# IO_V1_0.net
KiCad netlist of a schematic drawn in EAGLE
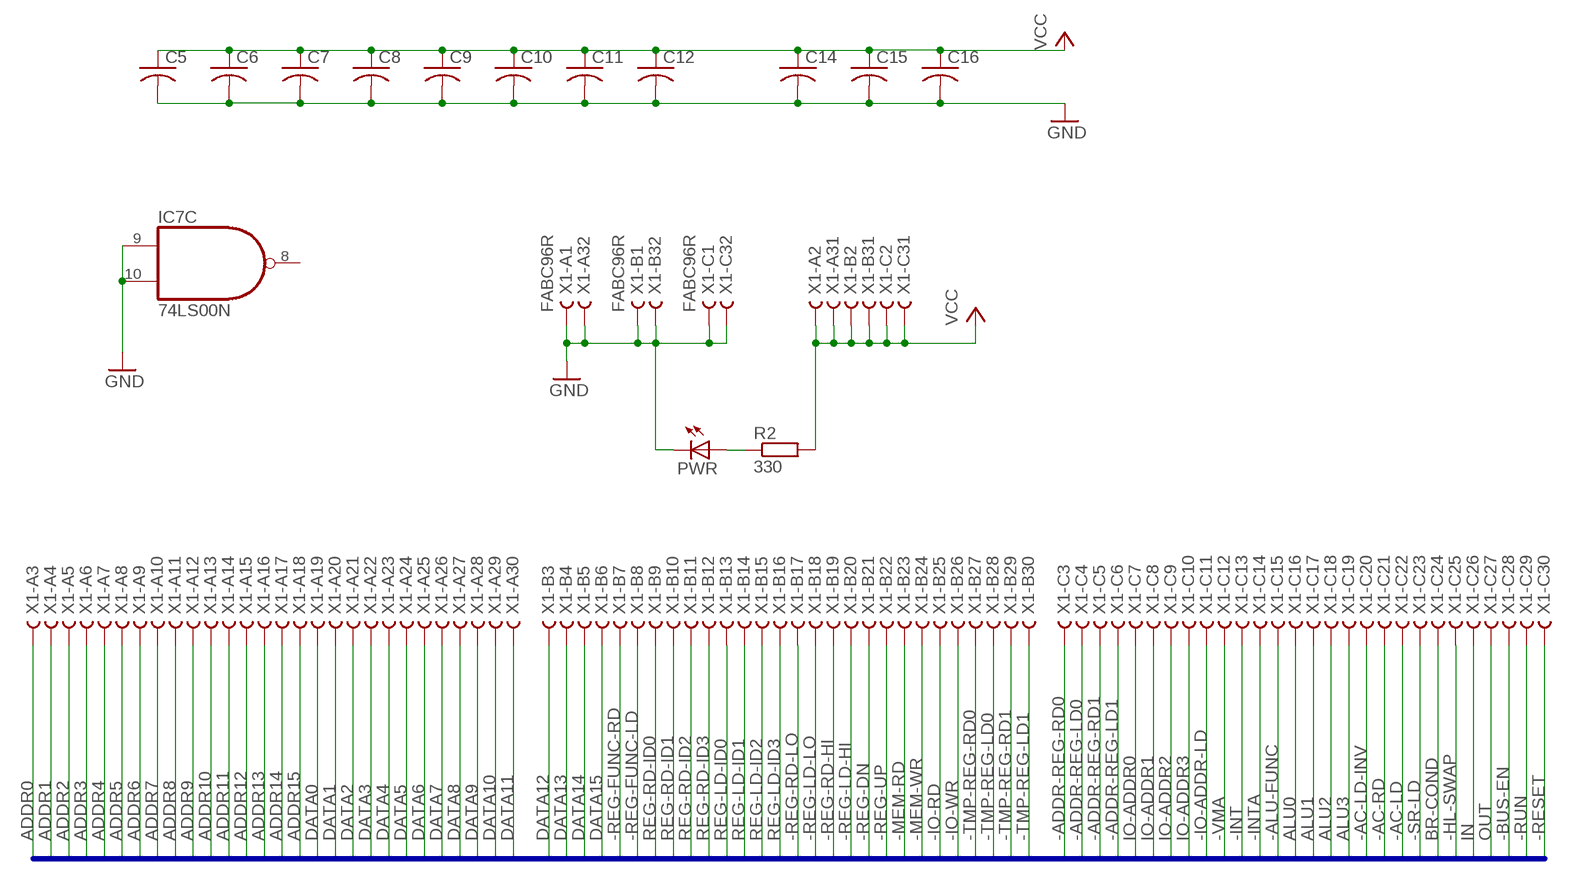
[diagram p0: schematic, sheet 1]
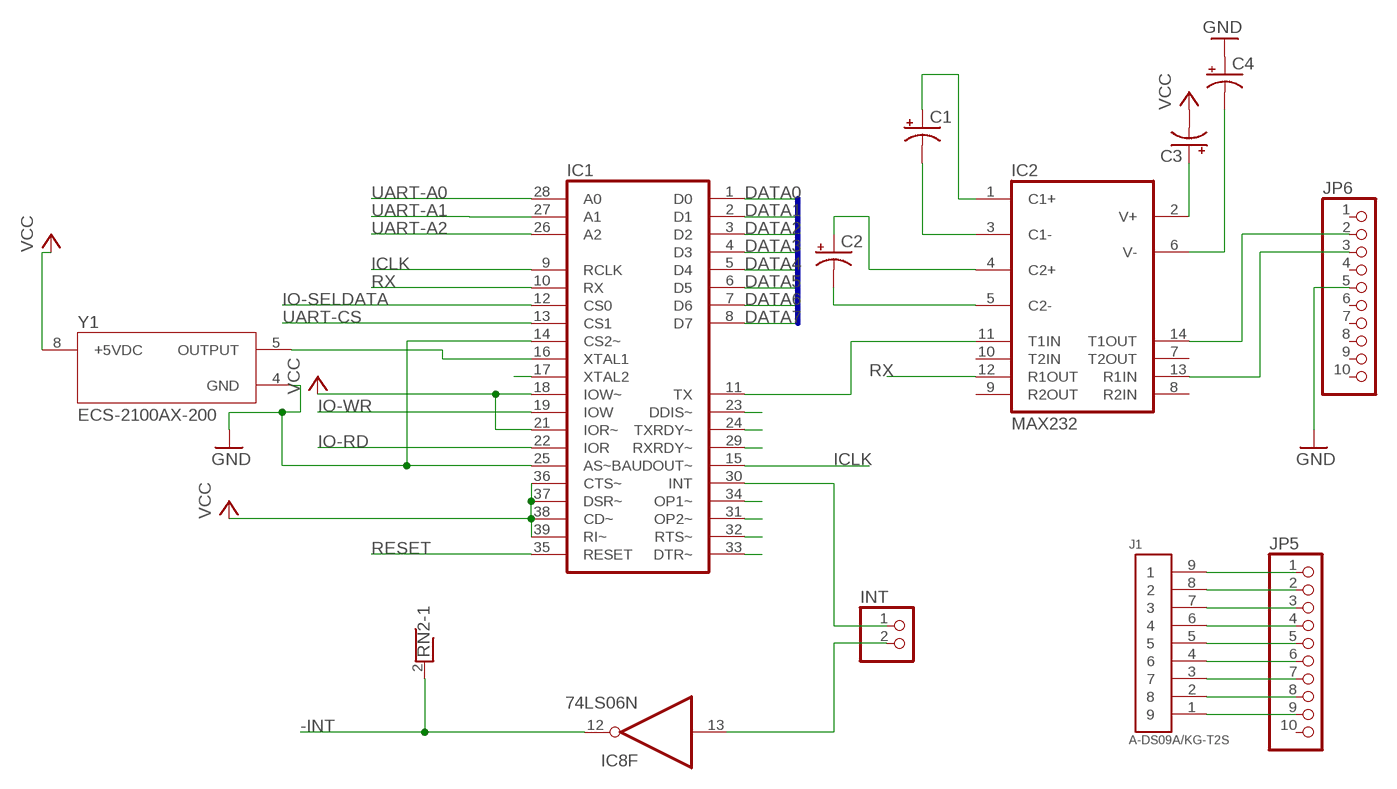
[diagram p1: schematic, sheet 2]
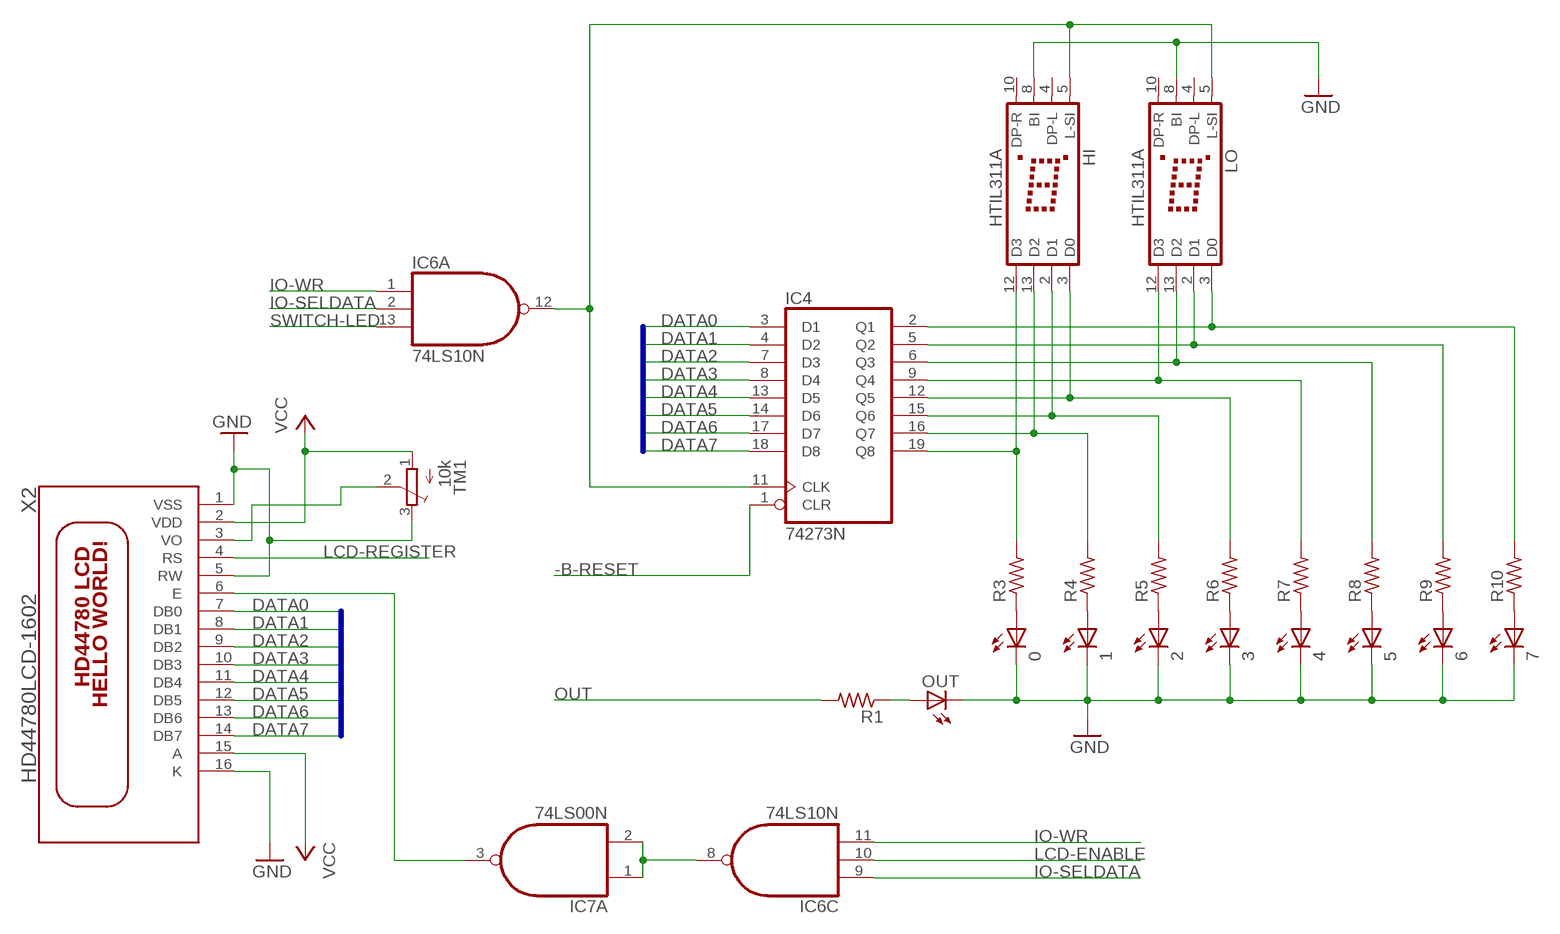
[diagram p2: schematic, sheet 3]
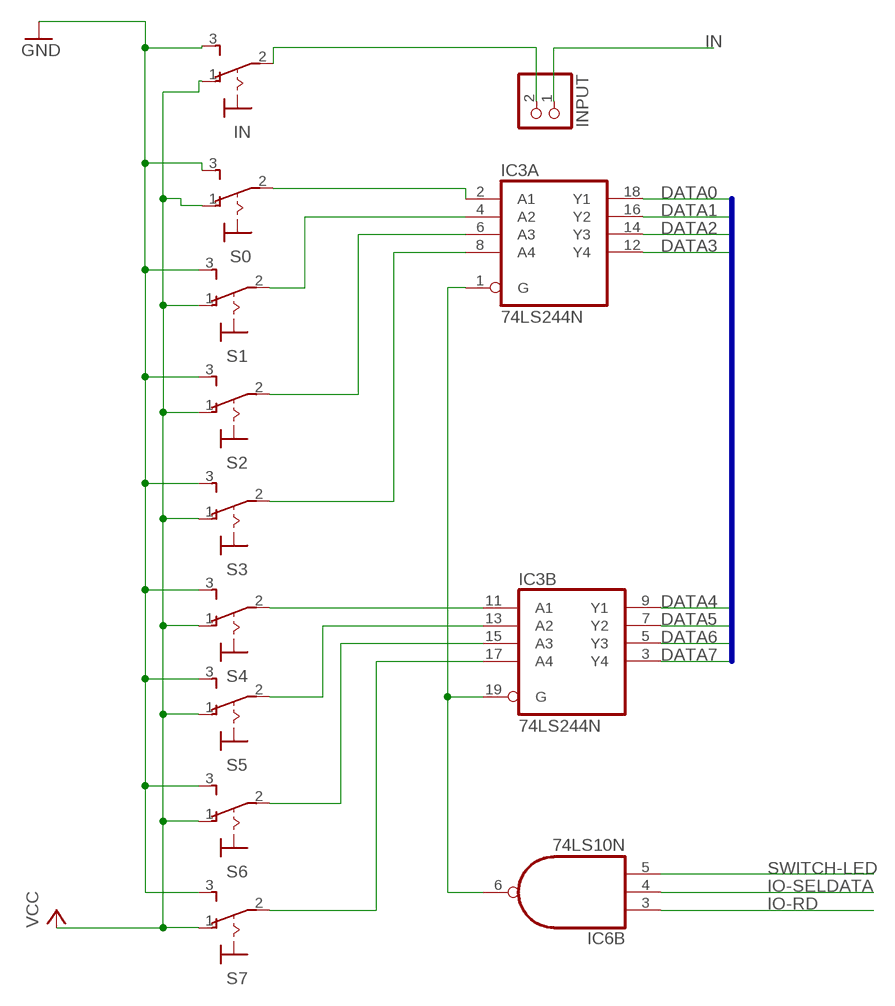
[diagram p3: schematic, sheet 4]
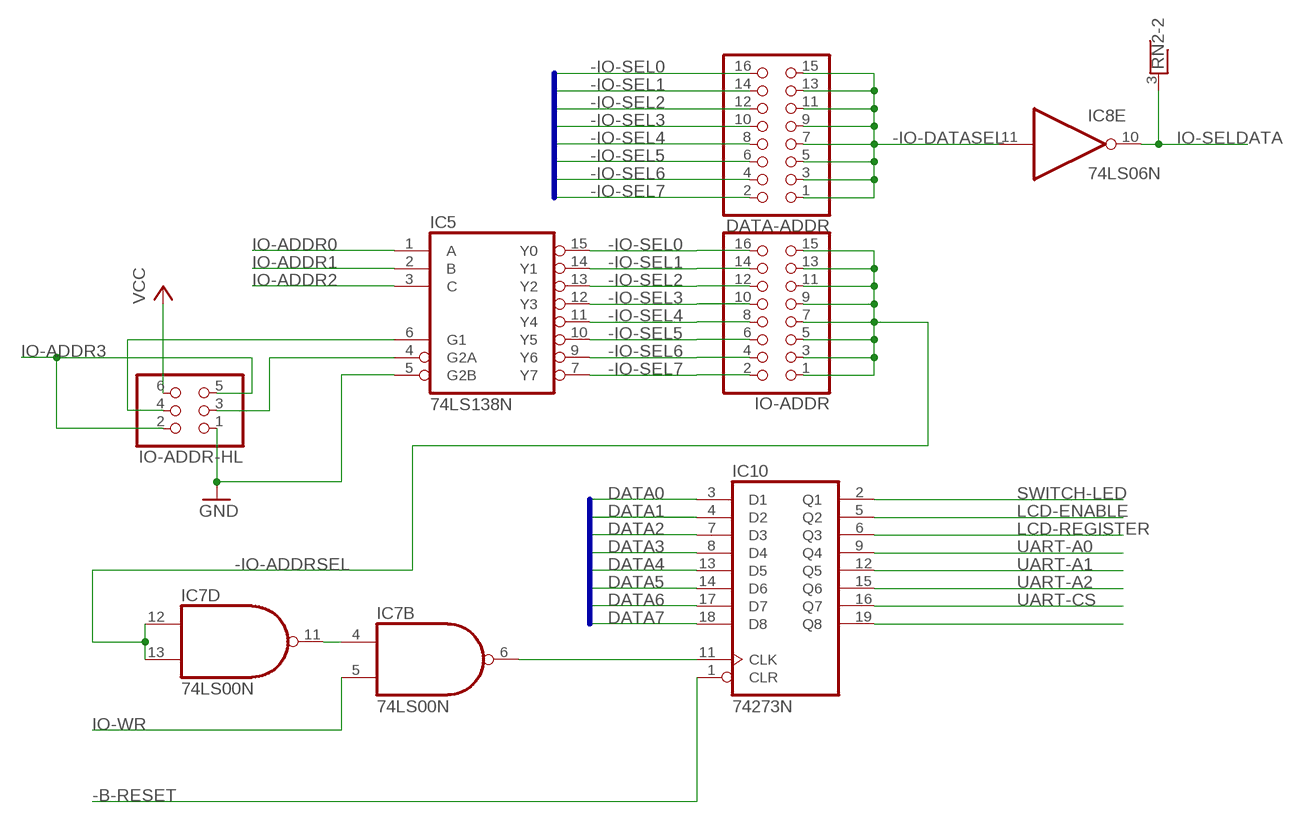
[diagram p4: schematic, sheet 5]
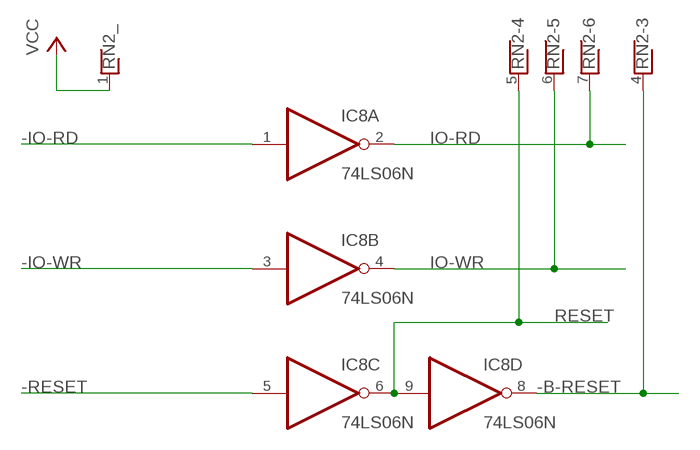
[diagram p5: schematic, sheet 6]

(export (version "E")
  (design (tool "Eeschema 10.0.6"))
  (components
    (comp (ref "C5")
      (value "C-US025-024X044")
      (footprint "eagle-import:C025-024X044")
      (libsource (lib "eagle-import") (part "C-US025-024X044"))
    )
    (comp (ref "C6")
      (value "C-US025-024X044")
      (footprint "eagle-import:C025-024X044")
      (libsource (lib "eagle-import") (part "C-US025-024X044"))
    )
    (comp (ref "C7")
      (value "C-US025-024X044")
      (footprint "eagle-import:C025-024X044")
      (libsource (lib "eagle-import") (part "C-US025-024X044"))
    )
    (comp (ref "C8")
      (value "C-US025-024X044")
      (footprint "eagle-import:C025-024X044")
      (libsource (lib "eagle-import") (part "C-US025-024X044"))
    )
    (comp (ref "C9")
      (value "C-US025-024X044")
      (footprint "eagle-import:C025-024X044")
      (libsource (lib "eagle-import") (part "C-US025-024X044"))
    )
    (comp (ref "C10")
      (value "C-US025-024X044")
      (footprint "eagle-import:C025-024X044")
      (libsource (lib "eagle-import") (part "C-US025-024X044"))
    )
    (comp (ref "C11")
      (value "C-US025-024X044")
      (footprint "eagle-import:C025-024X044")
      (libsource (lib "eagle-import") (part "C-US025-024X044"))
    )
    (comp (ref "C12")
      (value "C-US025-024X044")
      (footprint "eagle-import:C025-024X044")
      (libsource (lib "eagle-import") (part "C-US025-024X044"))
    )
    (comp (ref "C14")
      (value "C-US025-024X044")
      (footprint "eagle-import:C025-024X044")
      (libsource (lib "eagle-import") (part "C-US025-024X044"))
    )
    (comp (ref "C15")
      (value "C-US025-024X044")
      (footprint "eagle-import:C025-024X044")
      (libsource (lib "eagle-import") (part "C-US025-024X044"))
    )
    (comp (ref "C16")
      (value "C-US025-024X044")
      (footprint "eagle-import:C025-024X044")
      (libsource (lib "eagle-import") (part "C-US025-024X044"))
    )
    (comp (ref "IC7")
      (value "74LS00N")
      (footprint "eagle-import:DIL14")
      (libsource (lib "eagle-import") (part "7400NLS"))
    )
    (comp (ref "PWR")
      (value "LED5MM")
      (footprint "eagle-import:LED5MM")
      (libsource (lib "eagle-import") (part "led_LED5MM"))
    )
    (comp (ref "R2")
      (value "330")
      (footprint "eagle-import:0207_10")
      (libsource (lib "eagle-import") (part "R0207/10"))
    )
    (comp (ref "X1")
      (value "FABC96R")
      (footprint "eagle-import:FABC96R")
      (libsource (lib "eagle-import") (part "FABC96R"))
    )
    (comp (ref "DATA-ADDR")
      (value "PINHD-2X8")
      (footprint "eagle-import:2X08")
      (libsource (lib "eagle-import") (part "PINHD-2X8"))
    )
    (comp (ref "IC5")
      (value "74LS138N")
      (footprint "eagle-import:DIL16")
      (libsource (lib "eagle-import") (part "74138NLS"))
    )
    (comp (ref "IC8")
      (value "74LS06N")
      (footprint "eagle-import:DIL14")
      (libsource (lib "eagle-import") (part "7406NLS"))
    )
    (comp (ref "IC10")
      (value "74273N")
      (footprint "eagle-import:DIL20")
      (libsource (lib "eagle-import") (part "74273N"))
    )
    (comp (ref "IO-ADDR")
      (value "PINHD-2X8")
      (footprint "eagle-import:2X08")
      (libsource (lib "eagle-import") (part "PINHD-2X8"))
    )
    (comp (ref "IO-ADDR-HL")
      (value "PINHD-2X3")
      (footprint "eagle-import:2X03")
      (libsource (lib "eagle-import") (part "PINHD-2X3"))
    )
    (comp (ref "RN2")
      (value "RNX6")
      (footprint "eagle-import:RN-7")
      (libsource (lib "eagle-import") (part "RNX6"))
    )
    (comp (ref "0")
      (value "LED5MM")
      (footprint "eagle-import:LED5MM")
      (libsource (lib "eagle-import") (part "LED5MM"))
    )
    (comp (ref "1")
      (value "LED5MM")
      (footprint "eagle-import:LED5MM")
      (libsource (lib "eagle-import") (part "LED5MM"))
    )
    (comp (ref "2")
      (value "LED5MM")
      (footprint "eagle-import:LED5MM")
      (libsource (lib "eagle-import") (part "LED5MM"))
    )
    (comp (ref "3")
      (value "LED5MM")
      (footprint "eagle-import:LED5MM")
      (libsource (lib "eagle-import") (part "LED5MM"))
    )
    (comp (ref "4")
      (value "LED5MM")
      (footprint "eagle-import:LED5MM")
      (libsource (lib "eagle-import") (part "LED5MM"))
    )
    (comp (ref "5")
      (value "LED5MM")
      (footprint "eagle-import:LED5MM")
      (libsource (lib "eagle-import") (part "LED5MM"))
    )
    (comp (ref "6")
      (value "LED5MM")
      (footprint "eagle-import:LED5MM")
      (libsource (lib "eagle-import") (part "LED5MM"))
    )
    (comp (ref "7")
      (value "LED5MM")
      (footprint "eagle-import:LED5MM")
      (libsource (lib "eagle-import") (part "LED5MM"))
    )
    (comp (ref "HI")
      (value "HTIL311A")
      (footprint "eagle-import:HTIL311A")
      (libsource (lib "eagle-import") (part "HTIL311A"))
    )
    (comp (ref "IC4")
      (value "74273N")
      (footprint "eagle-import:DIL20")
      (libsource (lib "eagle-import") (part "74273N"))
    )
    (comp (ref "IC6")
      (value "74LS10N")
      (footprint "eagle-import:DIL14")
      (libsource (lib "eagle-import") (part "7410NLS"))
    )
    (comp (ref "LO")
      (value "HTIL311A")
      (footprint "eagle-import:HTIL311A")
      (libsource (lib "eagle-import") (part "HTIL311A"))
    )
    (comp (ref "OUT")
      (value "LED5MM")
      (footprint "eagle-import:LED5MM")
      (libsource (lib "eagle-import") (part "LED5MM"))
    )
    (comp (ref "R1")
      (value "R-US_0207/10")
      (footprint "eagle-import:0207_10")
      (libsource (lib "eagle-import") (part "R-US_0207/10"))
    )
    (comp (ref "R3")
      (value "R-US_0207/10")
      (footprint "eagle-import:0207_10")
      (libsource (lib "eagle-import") (part "R-US_0207/10"))
    )
    (comp (ref "R4")
      (value "R-US_0207/10")
      (footprint "eagle-import:0207_10")
      (libsource (lib "eagle-import") (part "R-US_0207/10"))
    )
    (comp (ref "R5")
      (value "R-US_0207/10")
      (footprint "eagle-import:0207_10")
      (libsource (lib "eagle-import") (part "R-US_0207/10"))
    )
    (comp (ref "R6")
      (value "R-US_0207/10")
      (footprint "eagle-import:0207_10")
      (libsource (lib "eagle-import") (part "R-US_0207/10"))
    )
    (comp (ref "R7")
      (value "R-US_0207/10")
      (footprint "eagle-import:0207_10")
      (libsource (lib "eagle-import") (part "R-US_0207/10"))
    )
    (comp (ref "R8")
      (value "R-US_0207/10")
      (footprint "eagle-import:0207_10")
      (libsource (lib "eagle-import") (part "R-US_0207/10"))
    )
    (comp (ref "R9")
      (value "R-US_0207/10")
      (footprint "eagle-import:0207_10")
      (libsource (lib "eagle-import") (part "R-US_0207/10"))
    )
    (comp (ref "R10")
      (value "R-US_0207/10")
      (footprint "eagle-import:0207_10")
      (libsource (lib "eagle-import") (part "R-US_0207/10"))
    )
    (comp (ref "TM1")
      (value "10k")
      (footprint "eagle-import:TRIM-3386")
      (libsource (lib "eagle-import") (part "TRIMPOT3386"))
    )
    (comp (ref "X2")
      (value "HD44780LCD-1602")
      (footprint "eagle-import:LCD1602")
      (libsource (lib "eagle-import") (part "HD44780LCD-1602"))
    )
    (comp (ref "IC3")
      (value "74LS244N")
      (footprint "eagle-import:DIL20")
      (libsource (lib "eagle-import") (part "74xx-us_88_74244NLS"))
    )
    (comp (ref "IN")
      (value "M9040P")
      (footprint "eagle-import:M9040P")
      (libsource (lib "eagle-import") (part "M9040P"))
    )
    (comp (ref "INPUT")
      (value "PINHD-1X2")
      (footprint "eagle-import:1X02")
      (libsource (lib "eagle-import") (part "PINHD-1X2"))
    )
    (comp (ref "S0")
      (value "M9040P")
      (footprint "eagle-import:M9040P")
      (libsource (lib "eagle-import") (part "M9040P"))
    )
    (comp (ref "S1")
      (value "M9040P")
      (footprint "eagle-import:M9040P")
      (libsource (lib "eagle-import") (part "M9040P"))
    )
    (comp (ref "S2")
      (value "M9040P")
      (footprint "eagle-import:M9040P")
      (libsource (lib "eagle-import") (part "M9040P"))
    )
    (comp (ref "S3")
      (value "M9040P")
      (footprint "eagle-import:M9040P")
      (libsource (lib "eagle-import") (part "M9040P"))
    )
    (comp (ref "S4")
      (value "M9040P")
      (footprint "eagle-import:M9040P")
      (libsource (lib "eagle-import") (part "M9040P"))
    )
    (comp (ref "S5")
      (value "M9040P")
      (footprint "eagle-import:M9040P")
      (libsource (lib "eagle-import") (part "M9040P"))
    )
    (comp (ref "S6")
      (value "M9040P")
      (footprint "eagle-import:M9040P")
      (libsource (lib "eagle-import") (part "M9040P"))
    )
    (comp (ref "S7")
      (value "M9040P")
      (footprint "eagle-import:M9040P")
      (libsource (lib "eagle-import") (part "M9040P"))
    )
    (comp (ref "C1")
      (value "CPOL-USE2,5-6E")
      (footprint "eagle-import:E2,5-6E")
      (libsource (lib "eagle-import") (part "CPOL-USE2,5-6E"))
    )
    (comp (ref "C2")
      (value "CPOL-USE2,5-6E")
      (footprint "eagle-import:E2,5-6E")
      (libsource (lib "eagle-import") (part "CPOL-USE2,5-6E"))
    )
    (comp (ref "C3")
      (value "CPOL-USE2,5-6E")
      (footprint "eagle-import:E2,5-6E")
      (libsource (lib "eagle-import") (part "CPOL-USE2,5-6E"))
    )
    (comp (ref "C4")
      (value "CPOL-USE2,5-6E")
      (footprint "eagle-import:E2,5-6E")
      (libsource (lib "eagle-import") (part "CPOL-USE2,5-6E"))
    )
    (comp (ref "IC1")
      (value "XR-16C550P")
      (footprint "eagle-import:DIL40")
      (fields (field (name "MPN") "ST16C450CP40"))
      (libsource (lib "eagle-import") (part "XR-16C550P"))
    )
    (comp (ref "IC2")
      (value "MAX232")
      (footprint "eagle-import:DIL16")
      (fields (field (name "MF") "MAXIM") (field (name "MPN") "MAX232ACPE+"))
      (libsource (lib "eagle-import") (part "MAX232"))
    )
    (comp (ref "INT")
      (value "PINHD-1X2")
      (footprint "eagle-import:1X02")
      (libsource (lib "eagle-import") (part "PINHD-1X2"))
    )
    (comp (ref "J1")
      (value "A-DS09A/KG-T2S")
      (footprint "eagle-import:A-DS09A_KG-T2S")
      (fields
        (field (name "DIGI_KEY_PART_NUMBER") "AE10968-ND")
        (field (name "MANUFACTURER") "Assmann WSW Components")
        (field (name "MPN") "A-DS 09 A/KG-T2S")
        (field (name "CREATEDBY") "PCBLayout.com")
      )
      (libsource (lib "eagle-import") (part "A-DS09A/KG-T2S"))
    )
    (comp (ref "JP5")
      (value "PINHD-1X10")
      (footprint "eagle-import:1X10")
      (libsource (lib "eagle-import") (part "PINHD-1X10"))
    )
    (comp (ref "JP6")
      (value "PINHD-1X10")
      (footprint "eagle-import:1X10")
      (libsource (lib "eagle-import") (part "PINHD-1X10"))
    )
    (comp (ref "Y1")
      (value "ECS-2100AX-200")
      (footprint "eagle-import:ECS-2100AX-200")
      (fields
        (field (name "DIGIKEY_PART_NUMBER") "X964-ND")
        (field (name "MANUFACTURER") "ECS Inc.")
        (field (name "CREATED_BY") "PCBLayout.com")
      )
      (libsource (lib "eagle-import") (part "ECS-2100AX-200"))
    )
  )
  (nets
    (net (code "1") (name "-AC-LD") (class "Default")
      (node (ref "X1") (pin "C22") (pinfunction "B_C22") (pintype "passive"))
    )
    (net (code "2") (name "-AC-LD-INV") (class "Default")
      (node (ref "X1") (pin "C20") (pinfunction "B_C20") (pintype "passive"))
    )
    (net (code "3") (name "-AC-RD") (class "Default")
      (node (ref "X1") (pin "C21") (pinfunction "B_C21") (pintype "passive"))
    )
    (net (code "4") (name "-ADDR-REG-LD0") (class "Default")
      (node (ref "X1") (pin "C4") (pinfunction "B_C4") (pintype "passive"))
    )
    (net (code "5") (name "-ADDR-REG-LD1") (class "Default")
      (node (ref "X1") (pin "C6") (pinfunction "B_C6") (pintype "passive"))
    )
    (net (code "6") (name "-ADDR-REG-RD0") (class "Default")
      (node (ref "X1") (pin "C3") (pinfunction "B_C3") (pintype "passive"))
    )
    (net (code "7") (name "-ADDR-REG-RD1") (class "Default")
      (node (ref "X1") (pin "C5") (pinfunction "B_C5") (pintype "passive"))
    )
    (net (code "8") (name "-ALU-FUNC") (class "Default")
      (node (ref "X1") (pin "C15") (pinfunction "B_C15") (pintype "passive"))
    )
    (net (code "9") (name "-B-RESET") (class "Default")
      (node (ref "IC10") (pin "1") (pinfunction "CLR_1") (pintype "input"))
      (node (ref "IC4") (pin "1") (pinfunction "CLR_1") (pintype "input"))
      (node (ref "IC8") (pin "8") (pinfunction "O_8") (pintype "open_collector"))
      (node (ref "RN2") (pin "4") (pinfunction "1_4") (pintype "passive"))
    )
    (net (code "10") (name "-BUS-EN") (class "Default")
      (node (ref "X1") (pin "C28") (pinfunction "B_C28") (pintype "passive"))
    )
    (net (code "11") (name "-HL-SWAP") (class "Default")
      (node (ref "X1") (pin "C25") (pinfunction "B_C25") (pintype "passive"))
    )
    (net (code "12") (name "-INT") (class "Default")
      (node (ref "IC8") (pin "12") (pinfunction "O_12") (pintype "open_collector"))
      (node (ref "RN2") (pin "2") (pinfunction "1_2") (pintype "passive"))
      (node (ref "X1") (pin "C13") (pinfunction "B_C13") (pintype "passive"))
    )
    (net (code "13") (name "-INTA") (class "Default")
      (node (ref "X1") (pin "C14") (pinfunction "B_C14") (pintype "passive"))
    )
    (net (code "14") (name "-IO-ADDR-LD") (class "Default")
      (node (ref "X1") (pin "C11") (pinfunction "B_C11") (pintype "passive"))
    )
    (net (code "15") (name "-IO-ADDRSEL") (class "Default")
      (node (ref "IC7") (pin "12") (pinfunction "I0_12") (pintype "input"))
      (node (ref "IC7") (pin "13") (pinfunction "I1_13") (pintype "input"))
      (node (ref "IO-ADDR") (pin "1") (pinfunction "1_1") (pintype "passive"))
      (node (ref "IO-ADDR") (pin "11") (pinfunction "11_11") (pintype "passive"))
      (node (ref "IO-ADDR") (pin "13") (pinfunction "13_13") (pintype "passive"))
      (node (ref "IO-ADDR") (pin "15") (pinfunction "15_15") (pintype "passive"))
      (node (ref "IO-ADDR") (pin "3") (pinfunction "3_3") (pintype "passive"))
      (node (ref "IO-ADDR") (pin "5") (pinfunction "5_5") (pintype "passive"))
      (node (ref "IO-ADDR") (pin "7") (pinfunction "7_7") (pintype "passive"))
      (node (ref "IO-ADDR") (pin "9") (pinfunction "9_9") (pintype "passive"))
    )
    (net (code "16") (name "-IO-DATASEL") (class "Default")
      (node (ref "DATA-ADDR") (pin "1") (pinfunction "1_1") (pintype "passive"))
      (node (ref "DATA-ADDR") (pin "11") (pinfunction "11_11") (pintype "passive"))
      (node (ref "DATA-ADDR") (pin "13") (pinfunction "13_13") (pintype "passive"))
      (node (ref "DATA-ADDR") (pin "15") (pinfunction "15_15") (pintype "passive"))
      (node (ref "DATA-ADDR") (pin "3") (pinfunction "3_3") (pintype "passive"))
      (node (ref "DATA-ADDR") (pin "5") (pinfunction "5_5") (pintype "passive"))
      (node (ref "DATA-ADDR") (pin "7") (pinfunction "7_7") (pintype "passive"))
      (node (ref "DATA-ADDR") (pin "9") (pinfunction "9_9") (pintype "passive"))
      (node (ref "IC8") (pin "11") (pinfunction "I_11") (pintype "input"))
    )
    (net (code "17") (name "-IO-RD") (class "Default")
      (node (ref "IC8") (pin "1") (pinfunction "I_1") (pintype "input"))
      (node (ref "X1") (pin "B25") (pinfunction "B_B25") (pintype "passive"))
    )
    (net (code "18") (name "-IO-SEL0") (class "Default")
      (node (ref "DATA-ADDR") (pin "16") (pinfunction "16_16") (pintype "passive"))
      (node (ref "IC5") (pin "15") (pinfunction "Y0_15") (pintype "output"))
      (node (ref "IO-ADDR") (pin "16") (pinfunction "16_16") (pintype "passive"))
    )
    (net (code "19") (name "-IO-SEL1") (class "Default")
      (node (ref "DATA-ADDR") (pin "14") (pinfunction "14_14") (pintype "passive"))
      (node (ref "IC5") (pin "14") (pinfunction "Y1_14") (pintype "output"))
      (node (ref "IO-ADDR") (pin "14") (pinfunction "14_14") (pintype "passive"))
    )
    (net (code "20") (name "-IO-SEL2") (class "Default")
      (node (ref "DATA-ADDR") (pin "12") (pinfunction "12_12") (pintype "passive"))
      (node (ref "IC5") (pin "13") (pinfunction "Y2_13") (pintype "output"))
      (node (ref "IO-ADDR") (pin "12") (pinfunction "12_12") (pintype "passive"))
    )
    (net (code "21") (name "-IO-SEL3") (class "Default")
      (node (ref "DATA-ADDR") (pin "10") (pinfunction "10_10") (pintype "passive"))
      (node (ref "IC5") (pin "12") (pinfunction "Y3_12") (pintype "output"))
      (node (ref "IO-ADDR") (pin "10") (pinfunction "10_10") (pintype "passive"))
    )
    (net (code "22") (name "-IO-SEL4") (class "Default")
      (node (ref "DATA-ADDR") (pin "8") (pinfunction "8_8") (pintype "passive"))
      (node (ref "IC5") (pin "11") (pinfunction "Y4_11") (pintype "output"))
      (node (ref "IO-ADDR") (pin "8") (pinfunction "8_8") (pintype "passive"))
    )
    (net (code "23") (name "-IO-SEL5") (class "Default")
      (node (ref "DATA-ADDR") (pin "6") (pinfunction "6_6") (pintype "passive"))
      (node (ref "IC5") (pin "10") (pinfunction "Y5_10") (pintype "output"))
      (node (ref "IO-ADDR") (pin "6") (pinfunction "6_6") (pintype "passive"))
    )
    (net (code "24") (name "-IO-SEL6") (class "Default")
      (node (ref "DATA-ADDR") (pin "4") (pinfunction "4_4") (pintype "passive"))
      (node (ref "IC5") (pin "9") (pinfunction "Y6_9") (pintype "output"))
      (node (ref "IO-ADDR") (pin "4") (pinfunction "4_4") (pintype "passive"))
    )
    (net (code "25") (name "-IO-SEL7") (class "Default")
      (node (ref "DATA-ADDR") (pin "2") (pinfunction "2_2") (pintype "passive"))
      (node (ref "IC5") (pin "7") (pinfunction "Y7_7") (pintype "output"))
      (node (ref "IO-ADDR") (pin "2") (pinfunction "2_2") (pintype "passive"))
    )
    (net (code "26") (name "-IO-WR") (class "Default")
      (node (ref "IC8") (pin "3") (pinfunction "I_3") (pintype "input"))
      (node (ref "X1") (pin "B26") (pinfunction "B_B26") (pintype "passive"))
    )
    (net (code "27") (name "-MEM-RD") (class "Default")
      (node (ref "X1") (pin "B23") (pinfunction "B_B23") (pintype "passive"))
    )
    (net (code "28") (name "-MEM-WR") (class "Default")
      (node (ref "X1") (pin "B24") (pinfunction "B_B24") (pintype "passive"))
    )
    (net (code "29") (name "-REG-DN") (class "Default")
      (node (ref "X1") (pin "B21") (pinfunction "B_B21") (pintype "passive"))
    )
    (net (code "30") (name "-REG-FUNC-LD") (class "Default")
      (node (ref "X1") (pin "B8") (pinfunction "B_B8") (pintype "passive"))
    )
    (net (code "31") (name "-REG-FUNC-RD") (class "Default")
      (node (ref "X1") (pin "B7") (pinfunction "B_B7") (pintype "passive"))
    )
    (net (code "32") (name "-REG-LD-HI") (class "Default")
      (node (ref "X1") (pin "B20") (pinfunction "B_B20") (pintype "passive"))
    )
    (net (code "33") (name "-REG-LD-LO") (class "Default")
      (node (ref "X1") (pin "B18") (pinfunction "B_B18") (pintype "passive"))
    )
    (net (code "34") (name "-REG-RD-HI") (class "Default")
      (node (ref "X1") (pin "B19") (pinfunction "B_B19") (pintype "passive"))
    )
    (net (code "35") (name "-REG-RD-LO") (class "Default")
      (node (ref "X1") (pin "B17") (pinfunction "B_B17") (pintype "passive"))
    )
    (net (code "36") (name "-REG-UP") (class "Default")
      (node (ref "X1") (pin "B22") (pinfunction "B_B22") (pintype "passive"))
    )
    (net (code "37") (name "-RESET") (class "Default")
      (node (ref "IC8") (pin "5") (pinfunction "I_5") (pintype "input"))
      (node (ref "X1") (pin "C30") (pinfunction "B_C30") (pintype "passive"))
    )
    (net (code "38") (name "-RUN") (class "Default")
      (node (ref "X1") (pin "C29") (pinfunction "B_C29") (pintype "passive"))
    )
    (net (code "39") (name "-SR-LD") (class "Default")
      (node (ref "X1") (pin "C23") (pinfunction "B_C23") (pintype "passive"))
    )
    (net (code "40") (name "-TMP-REG-LD0") (class "Default")
      (node (ref "X1") (pin "B28") (pinfunction "B_B28") (pintype "passive"))
    )
    (net (code "41") (name "-TMP-REG-LD1") (class "Default")
      (node (ref "X1") (pin "B30") (pinfunction "B_B30") (pintype "passive"))
    )
    (net (code "42") (name "-TMP-REG-RD0") (class "Default")
      (node (ref "X1") (pin "B27") (pinfunction "B_B27") (pintype "passive"))
    )
    (net (code "43") (name "-TMP-REG-RD1") (class "Default")
      (node (ref "X1") (pin "B29") (pinfunction "B_B29") (pintype "passive"))
    )
    (net (code "44") (name "-VMA") (class "Default")
      (node (ref "X1") (pin "C12") (pinfunction "B_C12") (pintype "passive"))
    )
    (net (code "45") (name "ADDR0") (class "Default")
      (node (ref "X1") (pin "A3") (pinfunction "B_A3") (pintype "passive"))
    )
    (net (code "46") (name "ADDR1") (class "Default")
      (node (ref "X1") (pin "A4") (pinfunction "B_A4") (pintype "passive"))
    )
    (net (code "47") (name "ADDR2") (class "Default")
      (node (ref "X1") (pin "A5") (pinfunction "B_A5") (pintype "passive"))
    )
    (net (code "48") (name "ADDR3") (class "Default")
      (node (ref "X1") (pin "A6") (pinfunction "B_A6") (pintype "passive"))
    )
    (net (code "49") (name "ADDR4") (class "Default")
      (node (ref "X1") (pin "A7") (pinfunction "B_A7") (pintype "passive"))
    )
    (net (code "50") (name "ADDR5") (class "Default")
      (node (ref "X1") (pin "A8") (pinfunction "B_A8") (pintype "passive"))
    )
    (net (code "51") (name "ADDR6") (class "Default")
      (node (ref "X1") (pin "A9") (pinfunction "B_A9") (pintype "passive"))
    )
    (net (code "52") (name "ADDR7") (class "Default")
      (node (ref "X1") (pin "A10") (pinfunction "B_A10") (pintype "passive"))
    )
    (net (code "53") (name "ADDR8") (class "Default")
      (node (ref "X1") (pin "A11") (pinfunction "B_A11") (pintype "passive"))
    )
    (net (code "54") (name "ADDR9") (class "Default")
      (node (ref "X1") (pin "A12") (pinfunction "B_A12") (pintype "passive"))
    )
    (net (code "55") (name "ADDR10") (class "Default")
      (node (ref "X1") (pin "A13") (pinfunction "B_A13") (pintype "passive"))
    )
    (net (code "56") (name "ADDR11") (class "Default")
      (node (ref "X1") (pin "A14") (pinfunction "B_A14") (pintype "passive"))
    )
    (net (code "57") (name "ADDR12") (class "Default")
      (node (ref "X1") (pin "A15") (pinfunction "B_A15") (pintype "passive"))
    )
    (net (code "58") (name "ADDR13") (class "Default")
      (node (ref "X1") (pin "A16") (pinfunction "B_A16") (pintype "passive"))
    )
    (net (code "59") (name "ADDR14") (class "Default")
      (node (ref "X1") (pin "A17") (pinfunction "B_A17") (pintype "passive"))
    )
    (net (code "60") (name "ADDR15") (class "Default")
      (node (ref "X1") (pin "A18") (pinfunction "B_A18") (pintype "passive"))
    )
    (net (code "61") (name "ALU0") (class "Default")
      (node (ref "X1") (pin "C16") (pinfunction "B_C16") (pintype "passive"))
    )
    (net (code "62") (name "ALU1") (class "Default")
      (node (ref "X1") (pin "C17") (pinfunction "B_C17") (pintype "passive"))
    )
    (net (code "63") (name "ALU2") (class "Default")
      (node (ref "X1") (pin "C18") (pinfunction "B_C18") (pintype "passive"))
    )
    (net (code "64") (name "ALU3") (class "Default")
      (node (ref "X1") (pin "C19") (pinfunction "B_C19") (pintype "passive"))
    )
    (net (code "65") (name "BR-COND") (class "Default")
      (node (ref "X1") (pin "C24") (pinfunction "B_C24") (pintype "passive"))
    )
    (net (code "66") (name "DATA0") (class "Default")
      (node (ref "IC1") (pin "1") (pinfunction "D0_1") (pintype "bidirectional"))
      (node (ref "IC10") (pin "3") (pinfunction "D1_3") (pintype "input"))
      (node (ref "IC3") (pin "18") (pinfunction "Y1_18") (pintype "tri_state"))
      (node (ref "IC4") (pin "3") (pinfunction "D1_3") (pintype "input"))
      (node (ref "X1") (pin "A19") (pinfunction "B_A19") (pintype "passive"))
      (node (ref "X2") (pin "7") (pinfunction "DB0_7") (pintype "bidirectional"))
    )
    (net (code "67") (name "DATA1") (class "Default")
      (node (ref "IC1") (pin "2") (pinfunction "D1_2") (pintype "bidirectional"))
      (node (ref "IC10") (pin "4") (pinfunction "D2_4") (pintype "input"))
      (node (ref "IC3") (pin "16") (pinfunction "Y2_16") (pintype "tri_state"))
      (node (ref "IC4") (pin "4") (pinfunction "D2_4") (pintype "input"))
      (node (ref "X1") (pin "A20") (pinfunction "B_A20") (pintype "passive"))
      (node (ref "X2") (pin "8") (pinfunction "DB1_8") (pintype "bidirectional"))
    )
    (net (code "68") (name "DATA2") (class "Default")
      (node (ref "IC1") (pin "3") (pinfunction "D2_3") (pintype "bidirectional"))
      (node (ref "IC10") (pin "7") (pinfunction "D3_7") (pintype "input"))
      (node (ref "IC3") (pin "14") (pinfunction "Y3_14") (pintype "tri_state"))
      (node (ref "IC4") (pin "7") (pinfunction "D3_7") (pintype "input"))
      (node (ref "X1") (pin "A21") (pinfunction "B_A21") (pintype "passive"))
      (node (ref "X2") (pin "9") (pinfunction "DB2_9") (pintype "bidirectional"))
    )
    (net (code "69") (name "DATA3") (class "Default")
      (node (ref "IC1") (pin "4") (pinfunction "D3_4") (pintype "bidirectional"))
      (node (ref "IC10") (pin "8") (pinfunction "D4_8") (pintype "input"))
      (node (ref "IC3") (pin "12") (pinfunction "Y4_12") (pintype "tri_state"))
      (node (ref "IC4") (pin "8") (pinfunction "D4_8") (pintype "input"))
      (node (ref "X1") (pin "A22") (pinfunction "B_A22") (pintype "passive"))
      (node (ref "X2") (pin "10") (pinfunction "DB3_10") (pintype "bidirectional"))
    )
    (net (code "70") (name "DATA4") (class "Default")
      (node (ref "IC1") (pin "5") (pinfunction "D4_5") (pintype "bidirectional"))
      (node (ref "IC10") (pin "13") (pinfunction "D5_13") (pintype "input"))
      (node (ref "IC3") (pin "9") (pinfunction "Y1_9") (pintype "tri_state"))
      (node (ref "IC4") (pin "13") (pinfunction "D5_13") (pintype "input"))
      (node (ref "X1") (pin "A23") (pinfunction "B_A23") (pintype "passive"))
      (node (ref "X2") (pin "11") (pinfunction "DB4_11") (pintype "bidirectional"))
    )
    (net (code "71") (name "DATA5") (class "Default")
      (node (ref "IC1") (pin "6") (pinfunction "D5_6") (pintype "bidirectional"))
      (node (ref "IC10") (pin "14") (pinfunction "D6_14") (pintype "input"))
      (node (ref "IC3") (pin "7") (pinfunction "Y2_7") (pintype "tri_state"))
      (node (ref "IC4") (pin "14") (pinfunction "D6_14") (pintype "input"))
      (node (ref "X1") (pin "A24") (pinfunction "B_A24") (pintype "passive"))
      (node (ref "X2") (pin "12") (pinfunction "DB5_12") (pintype "bidirectional"))
    )
    (net (code "72") (name "DATA6") (class "Default")
      (node (ref "IC1") (pin "7") (pinfunction "D6_7") (pintype "bidirectional"))
      (node (ref "IC10") (pin "17") (pinfunction "D7_17") (pintype "input"))
      (node (ref "IC3") (pin "5") (pinfunction "Y3_5") (pintype "tri_state"))
      (node (ref "IC4") (pin "17") (pinfunction "D7_17") (pintype "input"))
      (node (ref "X1") (pin "A25") (pinfunction "B_A25") (pintype "passive"))
      (node (ref "X2") (pin "13") (pinfunction "DB6_13") (pintype "bidirectional"))
    )
    (net (code "73") (name "DATA7") (class "Default")
      (node (ref "IC1") (pin "8") (pinfunction "D7_8") (pintype "bidirectional"))
      (node (ref "IC10") (pin "18") (pinfunction "D8_18") (pintype "input"))
      (node (ref "IC3") (pin "3") (pinfunction "Y4_3") (pintype "tri_state"))
      (node (ref "IC4") (pin "18") (pinfunction "D8_18") (pintype "input"))
      (node (ref "X1") (pin "A26") (pinfunction "B_A26") (pintype "passive"))
      (node (ref "X2") (pin "14") (pinfunction "DB7_14") (pintype "bidirectional"))
    )
    (net (code "74") (name "DATA8") (class "Default")
      (node (ref "X1") (pin "A27") (pinfunction "B_A27") (pintype "passive"))
    )
    (net (code "75") (name "DATA9") (class "Default")
      (node (ref "X1") (pin "A28") (pinfunction "B_A28") (pintype "passive"))
    )
    (net (code "76") (name "DATA10") (class "Default")
      (node (ref "X1") (pin "A29") (pinfunction "B_A29") (pintype "passive"))
    )
    (net (code "77") (name "DATA11") (class "Default")
      (node (ref "X1") (pin "A30") (pinfunction "B_A30") (pintype "passive"))
    )
    (net (code "78") (name "DATA12") (class "Default")
      (node (ref "X1") (pin "B3") (pinfunction "B_B3") (pintype "passive"))
    )
    (net (code "79") (name "DATA13") (class "Default")
      (node (ref "X1") (pin "B4") (pinfunction "B_B4") (pintype "passive"))
    )
    (net (code "80") (name "DATA14") (class "Default")
      (node (ref "X1") (pin "B5") (pinfunction "B_B5") (pintype "passive"))
    )
    (net (code "81") (name "DATA15") (class "Default")
      (node (ref "X1") (pin "B6") (pinfunction "B_B6") (pintype "passive"))
    )
    (net (code "82") (name "GND") (class "Default")
      (node (ref "0") (pin "K") (pinfunction "C_K") (pintype "passive"))
      (node (ref "1") (pin "K") (pinfunction "C_K") (pintype "passive"))
      (node (ref "2") (pin "K") (pinfunction "C_K") (pintype "passive"))
      (node (ref "3") (pin "K") (pinfunction "C_K") (pintype "passive"))
      (node (ref "4") (pin "K") (pinfunction "C_K") (pintype "passive"))
      (node (ref "5") (pin "K") (pinfunction "C_K") (pintype "passive"))
      (node (ref "6") (pin "K") (pinfunction "C_K") (pintype "passive"))
      (node (ref "7") (pin "K") (pinfunction "C_K") (pintype "passive"))
      (node (ref "C10") (pin "2") (pinfunction "2_2") (pintype "passive"))
      (node (ref "C11") (pin "2") (pinfunction "2_2") (pintype "passive"))
      (node (ref "C12") (pin "2") (pinfunction "2_2") (pintype "passive"))
      (node (ref "C14") (pin "2") (pinfunction "2_2") (pintype "passive"))
      (node (ref "C15") (pin "2") (pinfunction "2_2") (pintype "passive"))
      (node (ref "C16") (pin "2") (pinfunction "2_2") (pintype "passive"))
      (node (ref "C4") (pin "+") (pinfunction "+_+") (pintype "passive"))
      (node (ref "C5") (pin "2") (pinfunction "2_2") (pintype "passive"))
      (node (ref "C6") (pin "2") (pinfunction "2_2") (pintype "passive"))
      (node (ref "C7") (pin "2") (pinfunction "2_2") (pintype "passive"))
      (node (ref "C8") (pin "2") (pinfunction "2_2") (pintype "passive"))
      (node (ref "C9") (pin "2") (pinfunction "2_2") (pintype "passive"))
      (node (ref "HI") (pin "8") (pinfunction "BI_8") (pintype "input"))
      (node (ref "IC1") (pin "14") (pinfunction "CS2~{}_14") (pintype "input"))
      (node (ref "IC1") (pin "25") (pinfunction "AS~{}_25") (pintype "input"))
      (node (ref "IC5") (pin "5") (pinfunction "G2B_5") (pintype "input"))
      (node (ref "IC7") (pin "10") (pinfunction "I1_10") (pintype "input"))
      (node (ref "IC7") (pin "9") (pinfunction "I0_9") (pintype "input"))
      (node (ref "IN") (pin "3") (pinfunction "S_3") (pintype "passive"))
      (node (ref "IO-ADDR-HL") (pin "1") (pinfunction "1_1") (pintype "passive"))
      (node (ref "JP6") (pin "5") (pinfunction "5_5") (pintype "passive"))
      (node (ref "LO") (pin "8") (pinfunction "BI_8") (pintype "input"))
      (node (ref "OUT") (pin "K") (pinfunction "C_K") (pintype "passive"))
      (node (ref "PWR") (pin "K") (pinfunction "C_K") (pintype "passive"))
      (node (ref "S0") (pin "3") (pinfunction "S_3") (pintype "passive"))
      (node (ref "S1") (pin "3") (pinfunction "S_3") (pintype "passive"))
      (node (ref "S2") (pin "3") (pinfunction "S_3") (pintype "passive"))
      (node (ref "S3") (pin "3") (pinfunction "S_3") (pintype "passive"))
      (node (ref "S4") (pin "3") (pinfunction "S_3") (pintype "passive"))
      (node (ref "S5") (pin "3") (pinfunction "S_3") (pintype "passive"))
      (node (ref "S6") (pin "3") (pinfunction "S_3") (pintype "passive"))
      (node (ref "S7") (pin "3") (pinfunction "S_3") (pintype "passive"))
      (node (ref "TM1") (pin "3") (pinfunction "E_3") (pintype "passive"))
      (node (ref "X1") (pin "A1") (pinfunction "B_A1") (pintype "passive"))
      (node (ref "X1") (pin "A32") (pinfunction "B_A32") (pintype "passive"))
      (node (ref "X1") (pin "B1") (pinfunction "B_B1") (pintype "passive"))
      (node (ref "X1") (pin "B32") (pinfunction "B_B32") (pintype "passive"))
      (node (ref "X1") (pin "C1") (pinfunction "B_C1") (pintype "passive"))
      (node (ref "X1") (pin "C32") (pinfunction "B_C32") (pintype "passive"))
      (node (ref "X2") (pin "1") (pinfunction "VSS_1") (pintype "power_in"))
      (node (ref "X2") (pin "16") (pinfunction "K_16") (pintype "input"))
      (node (ref "X2") (pin "5") (pinfunction "RW_5") (pintype "input"))
      (node (ref "Y1") (pin "4") (pinfunction "GND_4") (pintype "power_in"))
    )
    (net (code "83") (name "ICLK") (class "Default")
      (node (ref "IC1") (pin "15") (pinfunction "BAUDOUT~{}_15") (pintype "output"))
      (node (ref "IC1") (pin "9") (pinfunction "RCLK_9") (pintype "input"))
    )
    (net (code "84") (name "IN") (class "Default")
      (node (ref "INPUT") (pin "1") (pinfunction "1_1") (pintype "passive"))
      (node (ref "X1") (pin "C26") (pinfunction "B_C26") (pintype "passive"))
    )
    (net (code "85") (name "IO-ADDR0") (class "Default")
      (node (ref "IC5") (pin "1") (pinfunction "A_1") (pintype "input"))
      (node (ref "X1") (pin "C7") (pinfunction "B_C7") (pintype "passive"))
    )
    (net (code "86") (name "IO-ADDR1") (class "Default")
      (node (ref "IC5") (pin "2") (pinfunction "B_2") (pintype "input"))
      (node (ref "X1") (pin "C8") (pinfunction "B_C8") (pintype "passive"))
    )
    (net (code "87") (name "IO-ADDR2") (class "Default")
      (node (ref "IC5") (pin "3") (pinfunction "C_3") (pintype "input"))
      (node (ref "X1") (pin "C9") (pinfunction "B_C9") (pintype "passive"))
    )
    (net (code "88") (name "IO-ADDR3") (class "Default")
      (node (ref "IO-ADDR-HL") (pin "2") (pinfunction "2_2") (pintype "passive"))
      (node (ref "IO-ADDR-HL") (pin "5") (pinfunction "5_5") (pintype "passive"))
      (node (ref "X1") (pin "C10") (pinfunction "B_C10") (pintype "passive"))
    )
    (net (code "89") (name "IO-RD") (class "Default")
      (node (ref "IC1") (pin "22") (pinfunction "IOR_22") (pintype "input"))
      (node (ref "IC6") (pin "3") (pinfunction "I0_3") (pintype "input"))
      (node (ref "IC8") (pin "2") (pinfunction "O_2") (pintype "open_collector"))
      (node (ref "RN2") (pin "7") (pinfunction "1_7") (pintype "passive"))
    )
    (net (code "90") (name "IO-SELDATA") (class "Default")
      (node (ref "IC1") (pin "12") (pinfunction "CS0_12") (pintype "input"))
      (node (ref "IC6") (pin "2") (pinfunction "I1_2") (pintype "input"))
      (node (ref "IC6") (pin "4") (pinfunction "I1_4") (pintype "input"))
      (node (ref "IC6") (pin "9") (pinfunction "I0_9") (pintype "input"))
      (node (ref "IC8") (pin "10") (pinfunction "O_10") (pintype "open_collector"))
      (node (ref "RN2") (pin "3") (pinfunction "1_3") (pintype "passive"))
    )
    (net (code "91") (name "IO-WR") (class "Default")
      (node (ref "IC1") (pin "19") (pinfunction "IOW_19") (pintype "input"))
      (node (ref "IC6") (pin "1") (pinfunction "I0_1") (pintype "input"))
      (node (ref "IC6") (pin "11") (pinfunction "I2_11") (pintype "input"))
      (node (ref "IC7") (pin "5") (pinfunction "I1_5") (pintype "input"))
      (node (ref "IC8") (pin "4") (pinfunction "O_4") (pintype "open_collector"))
      (node (ref "RN2") (pin "6") (pinfunction "1_6") (pintype "passive"))
    )
    (net (code "92") (name "LCD-ENABLE") (class "Default")
      (node (ref "IC10") (pin "5") (pinfunction "Q2_5") (pintype "output"))
      (node (ref "IC6") (pin "10") (pinfunction "I1_10") (pintype "input"))
    )
    (net (code "93") (name "LCD-REGISTER") (class "Default")
      (node (ref "IC10") (pin "6") (pinfunction "Q3_6") (pintype "output"))
      (node (ref "X2") (pin "4") (pinfunction "RS_4") (pintype "input"))
    )
    (net (code "94") (name "Net-(0-PadA)") (class "Default")
      (node (ref "0") (pin "A") (pinfunction "A_A") (pintype "passive"))
      (node (ref "R3") (pin "1") (pinfunction "1_1") (pintype "passive"))
    )
    (net (code "95") (name "Net-(1-PadA)") (class "Default")
      (node (ref "1") (pin "A") (pinfunction "A_A") (pintype "passive"))
      (node (ref "R4") (pin "1") (pinfunction "1_1") (pintype "passive"))
    )
    (net (code "96") (name "Net-(2-PadA)") (class "Default")
      (node (ref "2") (pin "A") (pinfunction "A_A") (pintype "passive"))
      (node (ref "R5") (pin "1") (pinfunction "1_1") (pintype "passive"))
    )
    (net (code "97") (name "Net-(3-PadA)") (class "Default")
      (node (ref "3") (pin "A") (pinfunction "A_A") (pintype "passive"))
      (node (ref "R6") (pin "1") (pinfunction "1_1") (pintype "passive"))
    )
    (net (code "98") (name "Net-(4-PadA)") (class "Default")
      (node (ref "4") (pin "A") (pinfunction "A_A") (pintype "passive"))
      (node (ref "R7") (pin "1") (pinfunction "1_1") (pintype "passive"))
    )
    (net (code "99") (name "Net-(5-PadA)") (class "Default")
      (node (ref "5") (pin "A") (pinfunction "A_A") (pintype "passive"))
      (node (ref "R8") (pin "1") (pinfunction "1_1") (pintype "passive"))
    )
    (net (code "100") (name "Net-(6-PadA)") (class "Default")
      (node (ref "6") (pin "A") (pinfunction "A_A") (pintype "passive"))
      (node (ref "R9") (pin "1") (pinfunction "1_1") (pintype "passive"))
    )
    (net (code "101") (name "Net-(7-PadA)") (class "Default")
      (node (ref "7") (pin "A") (pinfunction "A_A") (pintype "passive"))
      (node (ref "R10") (pin "1") (pinfunction "1_1") (pintype "passive"))
    )
    (net (code "102") (name "Net-(HIA-D0)") (class "Default")
      (node (ref "HI") (pin "3") (pinfunction "D0_3") (pintype "input"))
      (node (ref "IC4") (pin "12") (pinfunction "Q5_12") (pintype "output"))
      (node (ref "R6") (pin "2") (pinfunction "2_2") (pintype "passive"))
    )
    (net (code "103") (name "Net-(HIA-D1)") (class "Default")
      (node (ref "HI") (pin "2") (pinfunction "D1_2") (pintype "input"))
      (node (ref "IC4") (pin "15") (pinfunction "Q6_15") (pintype "output"))
      (node (ref "R5") (pin "2") (pinfunction "2_2") (pintype "passive"))
    )
    (net (code "104") (name "Net-(HIA-D2)") (class "Default")
      (node (ref "HI") (pin "13") (pinfunction "D2_13") (pintype "input"))
      (node (ref "IC4") (pin "16") (pinfunction "Q7_16") (pintype "output"))
      (node (ref "R4") (pin "2") (pinfunction "2_2") (pintype "passive"))
    )
    (net (code "105") (name "Net-(HIA-D3)") (class "Default")
      (node (ref "HI") (pin "12") (pinfunction "D3_12") (pintype "input"))
      (node (ref "IC4") (pin "19") (pinfunction "Q8_19") (pintype "output"))
      (node (ref "R3") (pin "2") (pinfunction "2_2") (pintype "passive"))
    )
    (net (code "106") (name "Net-(HIA-L-SI)") (class "Default")
      (node (ref "HI") (pin "5") (pinfunction "L-SI_5") (pintype "input"))
      (node (ref "IC4") (pin "11") (pinfunction "CLK_11") (pintype "input"))
      (node (ref "IC6") (pin "12") (pinfunction "O_12") (pintype "output"))
      (node (ref "LO") (pin "5") (pinfunction "L-SI_5") (pintype "input"))
    )
    (net (code "107") (name "Net-(IC1A-INT)") (class "Default")
      (node (ref "IC1") (pin "30") (pinfunction "INT_30") (pintype "output"))
      (node (ref "INT") (pin "1") (pinfunction "1_1") (pintype "passive"))
    )
    (net (code "108") (name "Net-(IC1A-TX)") (class "Default")
      (node (ref "IC1") (pin "11") (pinfunction "TX_11") (pintype "output"))
      (node (ref "IC2") (pin "11") (pinfunction "T1IN_11") (pintype "input"))
    )
    (net (code "109") (name "Net-(IC1A-XTAL1)") (class "Default")
      (node (ref "IC1") (pin "16") (pinfunction "XTAL1_16") (pintype "input"))
      (node (ref "Y1") (pin "5") (pinfunction "OUTPUT_5") (pintype "output"))
    )
    (net (code "110") (name "Net-(IC2A-C1+)") (class "Default")
      (node (ref "C1") (pin "+") (pinfunction "+_+") (pintype "passive"))
      (node (ref "IC2") (pin "1") (pinfunction "C1+_1") (pintype "bidirectional"))
    )
    (net (code "111") (name "Net-(IC2A-C1-)") (class "Default")
      (node (ref "C1") (pin "-") (pinfunction "-_-") (pintype "passive"))
      (node (ref "IC2") (pin "3") (pinfunction "C1-_3") (pintype "bidirectional"))
    )
    (net (code "112") (name "Net-(IC2A-C2+)") (class "Default")
      (node (ref "C2") (pin "+") (pinfunction "+_+") (pintype "passive"))
      (node (ref "IC2") (pin "4") (pinfunction "C2+_4") (pintype "bidirectional"))
    )
    (net (code "113") (name "Net-(IC2A-C2-)") (class "Default")
      (node (ref "C2") (pin "-") (pinfunction "-_-") (pintype "passive"))
      (node (ref "IC2") (pin "5") (pinfunction "C2-_5") (pintype "bidirectional"))
    )
    (net (code "114") (name "Net-(IC2A-R1IN)") (class "Default")
      (node (ref "IC2") (pin "13") (pinfunction "R1IN_13") (pintype "input"))
      (node (ref "JP6") (pin "3") (pinfunction "3_3") (pintype "passive"))
    )
    (net (code "115") (name "Net-(IC2A-T1OUT)") (class "Default")
      (node (ref "IC2") (pin "14") (pinfunction "T1OUT_14") (pintype "output"))
      (node (ref "JP6") (pin "2") (pinfunction "2_2") (pintype "passive"))
    )
    (net (code "116") (name "Net-(IC2A-V+)") (class "Default")
      (node (ref "C3") (pin "+") (pinfunction "+_+") (pintype "passive"))
      (node (ref "IC2") (pin "2") (pinfunction "V+_2") (pintype "bidirectional"))
    )
    (net (code "117") (name "Net-(IC2A-V-)") (class "Default")
      (node (ref "C4") (pin "-") (pinfunction "-_-") (pintype "passive"))
      (node (ref "IC2") (pin "6") (pinfunction "V-_6") (pintype "bidirectional"))
    )
    (net (code "118") (name "Net-(IC3A-A1)") (class "Default")
      (node (ref "IC3") (pin "2") (pinfunction "A1_2") (pintype "input"))
      (node (ref "S0") (pin "2") (pinfunction "P_2") (pintype "passive"))
    )
    (net (code "119") (name "Net-(IC3A-A2)") (class "Default")
      (node (ref "IC3") (pin "4") (pinfunction "A2_4") (pintype "input"))
      (node (ref "S1") (pin "2") (pinfunction "P_2") (pintype "passive"))
    )
    (net (code "120") (name "Net-(IC3A-A3)") (class "Default")
      (node (ref "IC3") (pin "6") (pinfunction "A3_6") (pintype "input"))
      (node (ref "S2") (pin "2") (pinfunction "P_2") (pintype "passive"))
    )
    (net (code "121") (name "Net-(IC3A-A4)") (class "Default")
      (node (ref "IC3") (pin "8") (pinfunction "A4_8") (pintype "input"))
      (node (ref "S3") (pin "2") (pinfunction "P_2") (pintype "passive"))
    )
    (net (code "122") (name "Net-(IC3A-G)") (class "Default")
      (node (ref "IC3") (pin "1") (pinfunction "G_1") (pintype "input"))
      (node (ref "IC3") (pin "19") (pinfunction "G_19") (pintype "input"))
      (node (ref "IC6") (pin "6") (pinfunction "O_6") (pintype "output"))
    )
    (net (code "123") (name "Net-(IC3B-A1)") (class "Default")
      (node (ref "IC3") (pin "11") (pinfunction "A1_11") (pintype "input"))
      (node (ref "S4") (pin "2") (pinfunction "P_2") (pintype "passive"))
    )
    (net (code "124") (name "Net-(IC3B-A2)") (class "Default")
      (node (ref "IC3") (pin "13") (pinfunction "A2_13") (pintype "input"))
      (node (ref "S5") (pin "2") (pinfunction "P_2") (pintype "passive"))
    )
    (net (code "125") (name "Net-(IC3B-A3)") (class "Default")
      (node (ref "IC3") (pin "15") (pinfunction "A3_15") (pintype "input"))
      (node (ref "S6") (pin "2") (pinfunction "P_2") (pintype "passive"))
    )
    (net (code "126") (name "Net-(IC3B-A4)") (class "Default")
      (node (ref "IC3") (pin "17") (pinfunction "A4_17") (pintype "input"))
      (node (ref "S7") (pin "2") (pinfunction "P_2") (pintype "passive"))
    )
    (net (code "127") (name "Net-(IC4A-Q1)") (class "Default")
      (node (ref "IC4") (pin "2") (pinfunction "Q1_2") (pintype "output"))
      (node (ref "LO") (pin "3") (pinfunction "D0_3") (pintype "input"))
      (node (ref "R10") (pin "2") (pinfunction "2_2") (pintype "passive"))
    )
    (net (code "128") (name "Net-(IC4A-Q2)") (class "Default")
      (node (ref "IC4") (pin "5") (pinfunction "Q2_5") (pintype "output"))
      (node (ref "LO") (pin "2") (pinfunction "D1_2") (pintype "input"))
      (node (ref "R9") (pin "2") (pinfunction "2_2") (pintype "passive"))
    )
    (net (code "129") (name "Net-(IC4A-Q3)") (class "Default")
      (node (ref "IC4") (pin "6") (pinfunction "Q3_6") (pintype "output"))
      (node (ref "LO") (pin "13") (pinfunction "D2_13") (pintype "input"))
      (node (ref "R8") (pin "2") (pinfunction "2_2") (pintype "passive"))
    )
    (net (code "130") (name "Net-(IC4A-Q4)") (class "Default")
      (node (ref "IC4") (pin "9") (pinfunction "Q4_9") (pintype "output"))
      (node (ref "LO") (pin "12") (pinfunction "D3_12") (pintype "input"))
      (node (ref "R7") (pin "2") (pinfunction "2_2") (pintype "passive"))
    )
    (net (code "131") (name "Net-(IC5A-G1)") (class "Default")
      (node (ref "IC5") (pin "6") (pinfunction "G1_6") (pintype "input"))
      (node (ref "IO-ADDR-HL") (pin "4") (pinfunction "4_4") (pintype "passive"))
    )
    (net (code "132") (name "Net-(IC5A-G2A)") (class "Default")
      (node (ref "IC5") (pin "4") (pinfunction "G2A_4") (pintype "input"))
      (node (ref "IO-ADDR-HL") (pin "3") (pinfunction "3_3") (pintype "passive"))
    )
    (net (code "133") (name "Net-(IC6C-O)") (class "Default")
      (node (ref "IC6") (pin "8") (pinfunction "O_8") (pintype "output"))
      (node (ref "IC7") (pin "1") (pinfunction "I0_1") (pintype "input"))
      (node (ref "IC7") (pin "2") (pinfunction "I1_2") (pintype "input"))
    )
    (net (code "134") (name "Net-(IC7A-O)") (class "Default")
      (node (ref "IC7") (pin "3") (pinfunction "O_3") (pintype "output"))
      (node (ref "X2") (pin "6") (pinfunction "E_6") (pintype "input"))
    )
    (net (code "135") (name "Net-(IC7B-I0)") (class "Default")
      (node (ref "IC7") (pin "11") (pinfunction "O_11") (pintype "output"))
      (node (ref "IC7") (pin "4") (pinfunction "I0_4") (pintype "input"))
    )
    (net (code "136") (name "Net-(IC8F-I)") (class "Default")
      (node (ref "IC8") (pin "13") (pinfunction "I_13") (pintype "input"))
      (node (ref "INT") (pin "2") (pinfunction "2_2") (pintype "passive"))
    )
    (net (code "137") (name "Net-(IC10A-CLK)") (class "Default")
      (node (ref "IC10") (pin "11") (pinfunction "CLK_11") (pintype "input"))
      (node (ref "IC7") (pin "6") (pinfunction "O_6") (pintype "output"))
    )
    (net (code "138") (name "Net-(IN-P)") (class "Default")
      (node (ref "IN") (pin "2") (pinfunction "P_2") (pintype "passive"))
      (node (ref "INPUT") (pin "2") (pinfunction "2_2") (pintype "passive"))
    )
    (net (code "139") (name "Net-(J1-1)") (class "Default")
      (node (ref "J1") (pin "9") (pinfunction "1_9") (pintype "passive"))
      (node (ref "JP5") (pin "1") (pinfunction "1_1") (pintype "passive"))
    )
    (net (code "140") (name "Net-(J1-2)") (class "Default")
      (node (ref "J1") (pin "8") (pinfunction "2_8") (pintype "passive"))
      (node (ref "JP5") (pin "2") (pinfunction "2_2") (pintype "passive"))
    )
    (net (code "141") (name "Net-(J1-3)") (class "Default")
      (node (ref "J1") (pin "7") (pinfunction "3_7") (pintype "passive"))
      (node (ref "JP5") (pin "3") (pinfunction "3_3") (pintype "passive"))
    )
    (net (code "142") (name "Net-(J1-4)") (class "Default")
      (node (ref "J1") (pin "6") (pinfunction "4_6") (pintype "passive"))
      (node (ref "JP5") (pin "4") (pinfunction "4_4") (pintype "passive"))
    )
    (net (code "143") (name "Net-(J1-6)") (class "Default")
      (node (ref "J1") (pin "4") (pinfunction "6_4") (pintype "passive"))
      (node (ref "JP5") (pin "6") (pinfunction "6_6") (pintype "passive"))
    )
    (net (code "144") (name "Net-(J1-7)") (class "Default")
      (node (ref "J1") (pin "3") (pinfunction "7_3") (pintype "passive"))
      (node (ref "JP5") (pin "7") (pinfunction "7_7") (pintype "passive"))
    )
    (net (code "145") (name "Net-(J1-8)") (class "Default")
      (node (ref "J1") (pin "2") (pinfunction "8_2") (pintype "passive"))
      (node (ref "JP5") (pin "8") (pinfunction "8_8") (pintype "passive"))
    )
    (net (code "146") (name "Net-(J1-9)") (class "Default")
      (node (ref "J1") (pin "1") (pinfunction "9_1") (pintype "passive"))
      (node (ref "JP5") (pin "9") (pinfunction "9_9") (pintype "passive"))
    )
    (net (code "147") (name "Net-(J1-Pad5)") (class "Default")
      (node (ref "J1") (pin "5") (pinfunction "5_5") (pintype "passive"))
      (node (ref "JP5") (pin "5") (pinfunction "5_5") (pintype "passive"))
    )
    (net (code "148") (name "Net-(OUT-PadA)") (class "Default")
      (node (ref "OUT") (pin "A") (pinfunction "A_A") (pintype "passive"))
      (node (ref "R1") (pin "1") (pinfunction "1_1") (pintype "passive"))
    )
    (net (code "149") (name "Net-(PWR-PadA)") (class "Default")
      (node (ref "PWR") (pin "A") (pinfunction "A_A") (pintype "passive"))
      (node (ref "R2") (pin "1") (pinfunction "1_1") (pintype "passive"))
    )
    (net (code "150") (name "Net-(TM1-S)") (class "Default")
      (node (ref "TM1") (pin "2") (pinfunction "S_2") (pintype "passive"))
      (node (ref "X2") (pin "3") (pinfunction "VO_3") (pintype "input"))
    )
    (net (code "151") (name "OUT") (class "Default")
      (node (ref "R1") (pin "2") (pinfunction "2_2") (pintype "passive"))
      (node (ref "X1") (pin "C27") (pinfunction "B_C27") (pintype "passive"))
    )
    (net (code "152") (name "REG-LD-ID0") (class "Default")
      (node (ref "X1") (pin "B13") (pinfunction "B_B13") (pintype "passive"))
    )
    (net (code "153") (name "REG-LD-ID1") (class "Default")
      (node (ref "X1") (pin "B14") (pinfunction "B_B14") (pintype "passive"))
    )
    (net (code "154") (name "REG-LD-ID2") (class "Default")
      (node (ref "X1") (pin "B15") (pinfunction "B_B15") (pintype "passive"))
    )
    (net (code "155") (name "REG-LD-ID3") (class "Default")
      (node (ref "X1") (pin "B16") (pinfunction "B_B16") (pintype "passive"))
    )
    (net (code "156") (name "REG-RD-ID0") (class "Default")
      (node (ref "X1") (pin "B9") (pinfunction "B_B9") (pintype "passive"))
    )
    (net (code "157") (name "REG-RD-ID1") (class "Default")
      (node (ref "X1") (pin "B10") (pinfunction "B_B10") (pintype "passive"))
    )
    (net (code "158") (name "REG-RD-ID2") (class "Default")
      (node (ref "X1") (pin "B11") (pinfunction "B_B11") (pintype "passive"))
    )
    (net (code "159") (name "REG-RD-ID3") (class "Default")
      (node (ref "X1") (pin "B12") (pinfunction "B_B12") (pintype "passive"))
    )
    (net (code "160") (name "RESET") (class "Default")
      (node (ref "IC1") (pin "35") (pinfunction "RESET_35") (pintype "input"))
      (node (ref "IC8") (pin "6") (pinfunction "O_6") (pintype "open_collector"))
      (node (ref "IC8") (pin "9") (pinfunction "I_9") (pintype "input"))
      (node (ref "RN2") (pin "5") (pinfunction "1_5") (pintype "passive"))
    )
    (net (code "161") (name "RX") (class "Default")
      (node (ref "IC1") (pin "10") (pinfunction "RX_10") (pintype "input"))
      (node (ref "IC2") (pin "12") (pinfunction "R1OUT_12") (pintype "output"))
    )
    (net (code "162") (name "SWITCH-LED") (class "Default")
      (node (ref "IC10") (pin "2") (pinfunction "Q1_2") (pintype "output"))
      (node (ref "IC6") (pin "13") (pinfunction "I2_13") (pintype "input"))
      (node (ref "IC6") (pin "5") (pinfunction "I2_5") (pintype "input"))
    )
    (net (code "163") (name "UART-A0") (class "Default")
      (node (ref "IC1") (pin "28") (pinfunction "A0_28") (pintype "input"))
      (node (ref "IC10") (pin "9") (pinfunction "Q4_9") (pintype "output"))
    )
    (net (code "164") (name "UART-A1") (class "Default")
      (node (ref "IC1") (pin "27") (pinfunction "A1_27") (pintype "input"))
      (node (ref "IC10") (pin "12") (pinfunction "Q5_12") (pintype "output"))
    )
    (net (code "165") (name "UART-A2") (class "Default")
      (node (ref "IC1") (pin "26") (pinfunction "A2_26") (pintype "input"))
      (node (ref "IC10") (pin "15") (pinfunction "Q6_15") (pintype "output"))
    )
    (net (code "166") (name "UART-CS") (class "Default")
      (node (ref "IC1") (pin "13") (pinfunction "CS1_13") (pintype "input"))
      (node (ref "IC10") (pin "16") (pinfunction "Q7_16") (pintype "output"))
    )
    (net (code "167") (name "VCC") (class "Default")
      (node (ref "C10") (pin "1") (pinfunction "1_1") (pintype "passive"))
      (node (ref "C11") (pin "1") (pinfunction "1_1") (pintype "passive"))
      (node (ref "C12") (pin "1") (pinfunction "1_1") (pintype "passive"))
      (node (ref "C14") (pin "1") (pinfunction "1_1") (pintype "passive"))
      (node (ref "C15") (pin "1") (pinfunction "1_1") (pintype "passive"))
      (node (ref "C16") (pin "1") (pinfunction "1_1") (pintype "passive"))
      (node (ref "C3") (pin "-") (pinfunction "-_-") (pintype "passive"))
      (node (ref "C5") (pin "1") (pinfunction "1_1") (pintype "passive"))
      (node (ref "C6") (pin "1") (pinfunction "1_1") (pintype "passive"))
      (node (ref "C7") (pin "1") (pinfunction "1_1") (pintype "passive"))
      (node (ref "C8") (pin "1") (pinfunction "1_1") (pintype "passive"))
      (node (ref "C9") (pin "1") (pinfunction "1_1") (pintype "passive"))
      (node (ref "IC1") (pin "18") (pinfunction "IOW~{}_18") (pintype "input"))
      (node (ref "IC1") (pin "21") (pinfunction "IOR~{}_21") (pintype "input"))
      (node (ref "IC1") (pin "36") (pinfunction "CTS~{}_36") (pintype "input"))
      (node (ref "IC1") (pin "37") (pinfunction "DSR~{}_37") (pintype "input"))
      (node (ref "IC1") (pin "38") (pinfunction "CD~{}_38") (pintype "input"))
      (node (ref "IC1") (pin "39") (pinfunction "RI~{}_39") (pintype "input"))
      (node (ref "IN") (pin "1") (pinfunction "O_1") (pintype "passive"))
      (node (ref "IO-ADDR-HL") (pin "6") (pinfunction "6_6") (pintype "passive"))
      (node (ref "R2") (pin "2") (pinfunction "2_2") (pintype "passive"))
      (node (ref "RN2") (pin "1") (pinfunction "1_1") (pintype "passive"))
      (node (ref "S0") (pin "1") (pinfunction "O_1") (pintype "passive"))
      (node (ref "S1") (pin "1") (pinfunction "O_1") (pintype "passive"))
      (node (ref "S2") (pin "1") (pinfunction "O_1") (pintype "passive"))
      (node (ref "S3") (pin "1") (pinfunction "O_1") (pintype "passive"))
      (node (ref "S4") (pin "1") (pinfunction "O_1") (pintype "passive"))
      (node (ref "S5") (pin "1") (pinfunction "O_1") (pintype "passive"))
      (node (ref "S6") (pin "1") (pinfunction "O_1") (pintype "passive"))
      (node (ref "S7") (pin "1") (pinfunction "O_1") (pintype "passive"))
      (node (ref "TM1") (pin "1") (pinfunction "A_1") (pintype "passive"))
      (node (ref "X1") (pin "A2") (pinfunction "B_A2") (pintype "passive"))
      (node (ref "X1") (pin "A31") (pinfunction "B_A31") (pintype "passive"))
      (node (ref "X1") (pin "B2") (pinfunction "B_B2") (pintype "passive"))
      (node (ref "X1") (pin "B31") (pinfunction "B_B31") (pintype "passive"))
      (node (ref "X1") (pin "C2") (pinfunction "B_C2") (pintype "passive"))
      (node (ref "X1") (pin "C31") (pinfunction "B_C31") (pintype "passive"))
      (node (ref "X2") (pin "15") (pinfunction "A_15") (pintype "input"))
      (node (ref "X2") (pin "2") (pinfunction "VDD_2") (pintype "power_in"))
      (node (ref "Y1") (pin "8") (pinfunction "+5VDC_8") (pintype "input"))
    )
    (net (code "168") (name "unconnected-(HIA-DP-L-Pad4)") (class "Default")
      (node (ref "HI") (pin "4") (pinfunction "DP-L_4") (pintype "input"))
    )
    (net (code "169") (name "unconnected-(HIA-DP-R-Pad10)") (class "Default")
      (node (ref "HI") (pin "10") (pinfunction "DP-R_10") (pintype "input"))
    )
    (net (code "170") (name "unconnected-(IC1A-DDIS~{}-Pad23)") (class "Default")
      (node (ref "IC1") (pin "23") (pinfunction "DDIS~{}_23") (pintype "output"))
    )
    (net (code "171") (name "unconnected-(IC1A-DTR~{}-Pad33)") (class "Default")
      (node (ref "IC1") (pin "33") (pinfunction "DTR~{}_33") (pintype "output"))
    )
    (net (code "172") (name "unconnected-(IC1A-OP1~{}-Pad34)") (class "Default")
      (node (ref "IC1") (pin "34") (pinfunction "OP1~{}_34") (pintype "output"))
    )
    (net (code "173") (name "unconnected-(IC1A-OP2~{}-Pad31)") (class "Default")
      (node (ref "IC1") (pin "31") (pinfunction "OP2~{}_31") (pintype "output"))
    )
    (net (code "174") (name "unconnected-(IC1A-RTS~{}-Pad32)") (class "Default")
      (node (ref "IC1") (pin "32") (pinfunction "RTS~{}_32") (pintype "output"))
    )
    (net (code "175") (name "unconnected-(IC1A-RXRDY~{}-Pad29)") (class "Default")
      (node (ref "IC1") (pin "29") (pinfunction "RXRDY~{}_29") (pintype "output"))
    )
    (net (code "176") (name "unconnected-(IC1A-TXRDY~{}-Pad24)") (class "Default")
      (node (ref "IC1") (pin "24") (pinfunction "TXRDY~{}_24") (pintype "output"))
    )
    (net (code "177") (name "unconnected-(IC1A-XTAL2-Pad17)") (class "Default")
      (node (ref "IC1") (pin "17") (pinfunction "XTAL2_17") (pintype "input"))
    )
    (net (code "178") (name "unconnected-(IC2A-R2IN-Pad8)") (class "Default")
      (node (ref "IC2") (pin "8") (pinfunction "R2IN_8") (pintype "input"))
    )
    (net (code "179") (name "unconnected-(IC2A-R2OUT-Pad9)") (class "Default")
      (node (ref "IC2") (pin "9") (pinfunction "R2OUT_9") (pintype "output"))
    )
    (net (code "180") (name "unconnected-(IC2A-T2IN-Pad10)") (class "Default")
      (node (ref "IC2") (pin "10") (pinfunction "T2IN_10") (pintype "input"))
    )
    (net (code "181") (name "unconnected-(IC2A-T2OUT-Pad7)") (class "Default")
      (node (ref "IC2") (pin "7") (pinfunction "T2OUT_7") (pintype "output"))
    )
    (net (code "182") (name "unconnected-(IC7C-O-Pad8)") (class "Default")
      (node (ref "IC7") (pin "8") (pinfunction "O_8") (pintype "output"))
    )
    (net (code "183") (name "unconnected-(IC10A-Q8-Pad19)") (class "Default")
      (node (ref "IC10") (pin "19") (pinfunction "Q8_19") (pintype "output"))
    )
    (net (code "184") (name "unconnected-(JP5-Pad10)") (class "Default")
      (node (ref "JP5") (pin "10") (pinfunction "10_10") (pintype "passive"))
    )
    (net (code "185") (name "unconnected-(JP6-Pad1)") (class "Default")
      (node (ref "JP6") (pin "1") (pinfunction "1_1") (pintype "passive"))
    )
    (net (code "186") (name "unconnected-(JP6-Pad4)") (class "Default")
      (node (ref "JP6") (pin "4") (pinfunction "4_4") (pintype "passive"))
    )
    (net (code "187") (name "unconnected-(JP6-Pad6)") (class "Default")
      (node (ref "JP6") (pin "6") (pinfunction "6_6") (pintype "passive"))
    )
    (net (code "188") (name "unconnected-(JP6-Pad7)") (class "Default")
      (node (ref "JP6") (pin "7") (pinfunction "7_7") (pintype "passive"))
    )
    (net (code "189") (name "unconnected-(JP6-Pad8)") (class "Default")
      (node (ref "JP6") (pin "8") (pinfunction "8_8") (pintype "passive"))
    )
    (net (code "190") (name "unconnected-(JP6-Pad9)") (class "Default")
      (node (ref "JP6") (pin "9") (pinfunction "9_9") (pintype "passive"))
    )
    (net (code "191") (name "unconnected-(JP6-Pad10)") (class "Default")
      (node (ref "JP6") (pin "10") (pinfunction "10_10") (pintype "passive"))
    )
    (net (code "192") (name "unconnected-(LOA-DP-L-Pad4)") (class "Default")
      (node (ref "LO") (pin "4") (pinfunction "DP-L_4") (pintype "input"))
    )
    (net (code "193") (name "unconnected-(LOA-DP-R-Pad10)") (class "Default")
      (node (ref "LO") (pin "10") (pinfunction "DP-R_10") (pintype "input"))
    )
  )
)
